# apa102.net
KiCad netlist of a schematic drawn in EAGLE
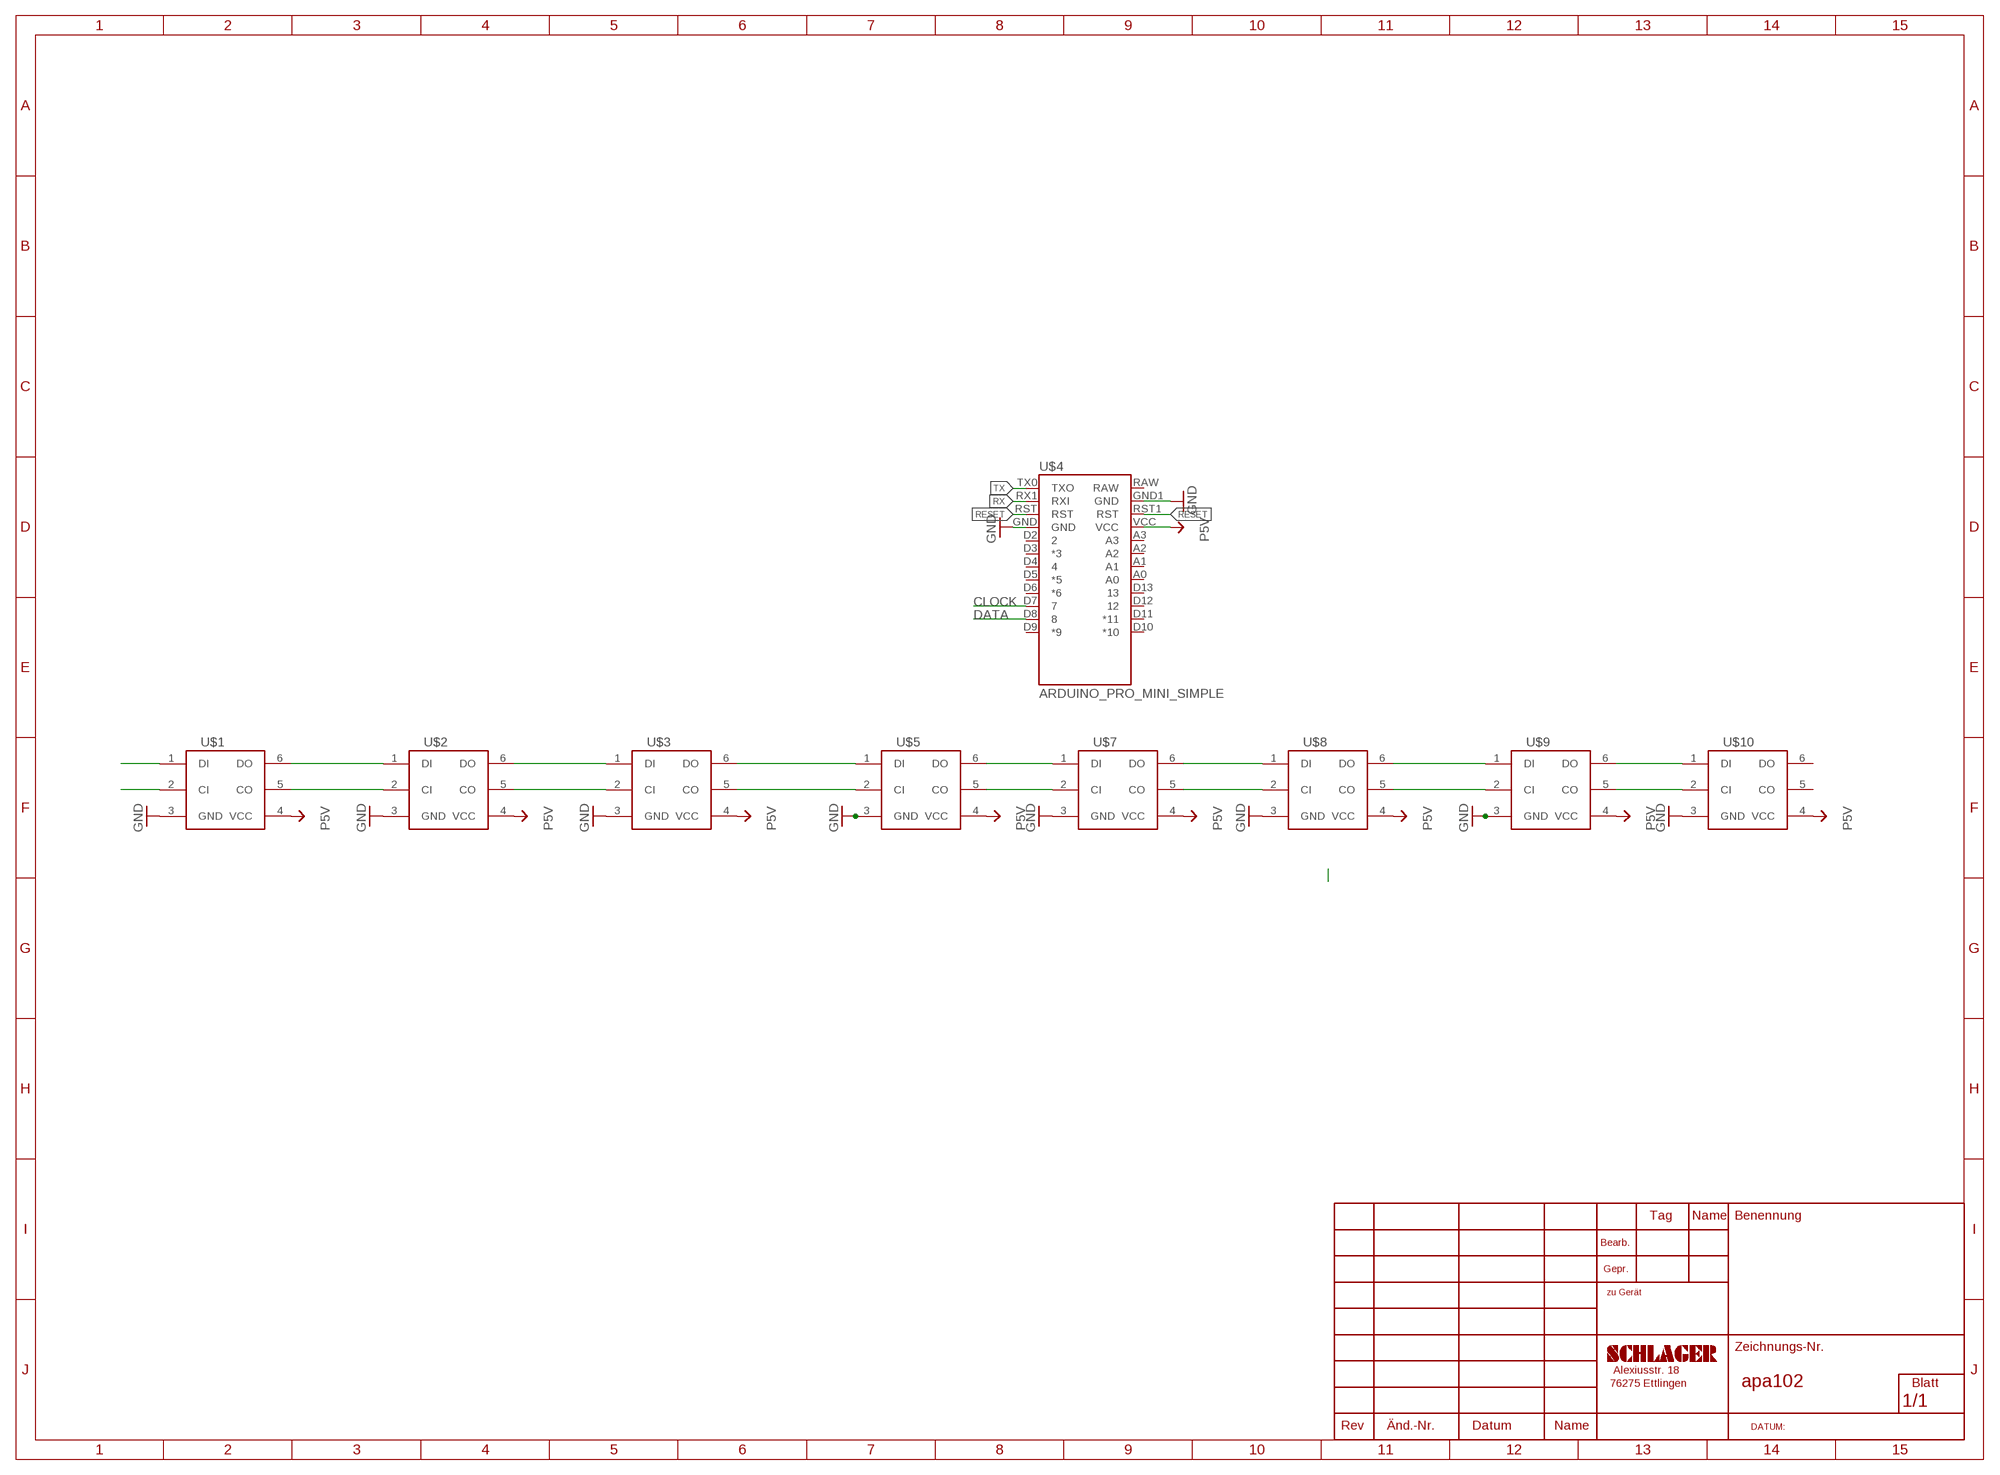
[diagram p0: schematic, sheet 1]

(export (version "E")
  (design (tool "Eeschema 10.0.6"))
  (components
    (comp (ref "U$1")
      (value "APA102")
      (footprint "eagle-import:LED5050")
      (libsource (lib "eagle-import") (part "APA102"))
    )
    (comp (ref "U$2")
      (value "APA102")
      (footprint "eagle-import:LED5050")
      (libsource (lib "eagle-import") (part "APA102"))
    )
    (comp (ref "U$3")
      (value "APA102")
      (footprint "eagle-import:LED5050")
      (libsource (lib "eagle-import") (part "APA102"))
    )
    (comp (ref "U$4")
      (value "ARDUINO_PRO_MINI_SIMPLE")
      (footprint "eagle-import:PRO_MINI_SIMPLE")
      (libsource (lib "eagle-import") (part "ARDUINO_PRO_MINI_SIMPLE"))
    )
    (comp (ref "U$5")
      (value "APA102")
      (footprint "eagle-import:LED5050")
      (libsource (lib "eagle-import") (part "APA102"))
    )
    (comp (ref "U$7")
      (value "APA102")
      (footprint "eagle-import:LED5050")
      (libsource (lib "eagle-import") (part "APA102"))
    )
    (comp (ref "U$8")
      (value "APA102")
      (footprint "eagle-import:LED5050")
      (libsource (lib "eagle-import") (part "APA102"))
    )
    (comp (ref "U$9")
      (value "APA102")
      (footprint "eagle-import:LED5050")
      (libsource (lib "eagle-import") (part "APA102"))
    )
    (comp (ref "U$10")
      (value "APA102")
      (footprint "eagle-import:LED5050")
      (libsource (lib "eagle-import") (part "APA102"))
    )
  )
  (nets
    (net (code "1") (name "/CLOCK") (class "Default")
      (node (ref "U$1") (pin "2") (pinfunction "CI_2") (pintype "bidirectional"))
      (node (ref "U$4") (pin "D7") (pinfunction "7_D7") (pintype "bidirectional"))
    )
    (net (code "2") (name "/DATA") (class "Default")
      (node (ref "U$1") (pin "1") (pinfunction "DI_1") (pintype "bidirectional"))
      (node (ref "U$4") (pin "D8") (pinfunction "8_D8") (pintype "bidirectional"))
    )
    (net (code "3") (name "GND") (class "Default")
      (node (ref "U$1") (pin "3") (pinfunction "GND_3") (pintype "bidirectional"))
      (node (ref "U$10") (pin "3") (pinfunction "GND_3") (pintype "bidirectional"))
      (node (ref "U$2") (pin "3") (pinfunction "GND_3") (pintype "bidirectional"))
      (node (ref "U$3") (pin "3") (pinfunction "GND_3") (pintype "bidirectional"))
      (node (ref "U$4") (pin "GND") (pinfunction "GND_GND") (pintype "bidirectional"))
      (node (ref "U$4") (pin "GND1") (pinfunction "GND_GND1") (pintype "bidirectional"))
      (node (ref "U$5") (pin "3") (pinfunction "GND_3") (pintype "bidirectional"))
      (node (ref "U$7") (pin "3") (pinfunction "GND_3") (pintype "bidirectional"))
      (node (ref "U$8") (pin "3") (pinfunction "GND_3") (pintype "bidirectional"))
      (node (ref "U$9") (pin "3") (pinfunction "GND_3") (pintype "bidirectional"))
    )
    (net (code "4") (name "Net-(U$1-CO)") (class "Default")
      (node (ref "U$1") (pin "5") (pinfunction "CO_5") (pintype "bidirectional"))
      (node (ref "U$2") (pin "2") (pinfunction "CI_2") (pintype "bidirectional"))
    )
    (net (code "5") (name "Net-(U$1-DO)") (class "Default")
      (node (ref "U$1") (pin "6") (pinfunction "DO_6") (pintype "bidirectional"))
      (node (ref "U$2") (pin "1") (pinfunction "DI_1") (pintype "bidirectional"))
    )
    (net (code "6") (name "Net-(U$2-CO)") (class "Default")
      (node (ref "U$2") (pin "5") (pinfunction "CO_5") (pintype "bidirectional"))
      (node (ref "U$3") (pin "2") (pinfunction "CI_2") (pintype "bidirectional"))
    )
    (net (code "7") (name "Net-(U$2-DO)") (class "Default")
      (node (ref "U$2") (pin "6") (pinfunction "DO_6") (pintype "bidirectional"))
      (node (ref "U$3") (pin "1") (pinfunction "DI_1") (pintype "bidirectional"))
    )
    (net (code "8") (name "Net-(U$3-CO)") (class "Default")
      (node (ref "U$3") (pin "5") (pinfunction "CO_5") (pintype "bidirectional"))
      (node (ref "U$5") (pin "2") (pinfunction "CI_2") (pintype "bidirectional"))
    )
    (net (code "9") (name "Net-(U$3-DO)") (class "Default")
      (node (ref "U$3") (pin "6") (pinfunction "DO_6") (pintype "bidirectional"))
      (node (ref "U$5") (pin "1") (pinfunction "DI_1") (pintype "bidirectional"))
    )
    (net (code "10") (name "Net-(U$5-CO)") (class "Default")
      (node (ref "U$5") (pin "5") (pinfunction "CO_5") (pintype "bidirectional"))
      (node (ref "U$7") (pin "2") (pinfunction "CI_2") (pintype "bidirectional"))
    )
    (net (code "11") (name "Net-(U$5-DO)") (class "Default")
      (node (ref "U$5") (pin "6") (pinfunction "DO_6") (pintype "bidirectional"))
      (node (ref "U$7") (pin "1") (pinfunction "DI_1") (pintype "bidirectional"))
    )
    (net (code "12") (name "Net-(U$7-CO)") (class "Default")
      (node (ref "U$7") (pin "5") (pinfunction "CO_5") (pintype "bidirectional"))
      (node (ref "U$8") (pin "2") (pinfunction "CI_2") (pintype "bidirectional"))
    )
    (net (code "13") (name "Net-(U$7-DO)") (class "Default")
      (node (ref "U$7") (pin "6") (pinfunction "DO_6") (pintype "bidirectional"))
      (node (ref "U$8") (pin "1") (pinfunction "DI_1") (pintype "bidirectional"))
    )
    (net (code "14") (name "Net-(U$8-CO)") (class "Default")
      (node (ref "U$8") (pin "5") (pinfunction "CO_5") (pintype "bidirectional"))
      (node (ref "U$9") (pin "2") (pinfunction "CI_2") (pintype "bidirectional"))
    )
    (net (code "15") (name "Net-(U$8-DO)") (class "Default")
      (node (ref "U$8") (pin "6") (pinfunction "DO_6") (pintype "bidirectional"))
      (node (ref "U$9") (pin "1") (pinfunction "DI_1") (pintype "bidirectional"))
    )
    (net (code "16") (name "Net-(U$10-CI)") (class "Default")
      (node (ref "U$10") (pin "2") (pinfunction "CI_2") (pintype "bidirectional"))
      (node (ref "U$9") (pin "5") (pinfunction "CO_5") (pintype "bidirectional"))
    )
    (net (code "17") (name "Net-(U$10-DI)") (class "Default")
      (node (ref "U$10") (pin "1") (pinfunction "DI_1") (pintype "bidirectional"))
      (node (ref "U$9") (pin "6") (pinfunction "DO_6") (pintype "bidirectional"))
    )
    (net (code "18") (name "P5V") (class "Default")
      (node (ref "U$1") (pin "4") (pinfunction "VCC_4") (pintype "bidirectional"))
      (node (ref "U$10") (pin "4") (pinfunction "VCC_4") (pintype "bidirectional"))
      (node (ref "U$2") (pin "4") (pinfunction "VCC_4") (pintype "bidirectional"))
      (node (ref "U$3") (pin "4") (pinfunction "VCC_4") (pintype "bidirectional"))
      (node (ref "U$4") (pin "VCC") (pinfunction "VCC_VCC") (pintype "bidirectional"))
      (node (ref "U$5") (pin "4") (pinfunction "VCC_4") (pintype "bidirectional"))
      (node (ref "U$7") (pin "4") (pinfunction "VCC_4") (pintype "bidirectional"))
      (node (ref "U$8") (pin "4") (pinfunction "VCC_4") (pintype "bidirectional"))
      (node (ref "U$9") (pin "4") (pinfunction "VCC_4") (pintype "bidirectional"))
    )
    (net (code "19") (name "RESET") (class "Default")
      (node (ref "U$4") (pin "RST") (pinfunction "RST_RST") (pintype "bidirectional"))
      (node (ref "U$4") (pin "RST1") (pinfunction "RST_RST1") (pintype "bidirectional"))
    )
    (net (code "20") (name "RX") (class "Default")
      (node (ref "U$4") (pin "RX1") (pinfunction "RXI_RX1") (pintype "bidirectional"))
    )
    (net (code "21") (name "TX") (class "Default")
      (node (ref "U$4") (pin "TX0") (pinfunction "TXO_TX0") (pintype "bidirectional"))
    )
    (net (code "22") (name "unconnected-(U$4-*3-PadD3)") (class "Default")
      (node (ref "U$4") (pin "D3") (pinfunction "*3_D3") (pintype "bidirectional"))
    )
    (net (code "23") (name "unconnected-(U$4-*5-PadD5)") (class "Default")
      (node (ref "U$4") (pin "D5") (pinfunction "*5_D5") (pintype "bidirectional"))
    )
    (net (code "24") (name "unconnected-(U$4-*6-PadD6)") (class "Default")
      (node (ref "U$4") (pin "D6") (pinfunction "*6_D6") (pintype "bidirectional"))
    )
    (net (code "25") (name "unconnected-(U$4-*9-PadD9)") (class "Default")
      (node (ref "U$4") (pin "D9") (pinfunction "*9_D9") (pintype "bidirectional"))
    )
    (net (code "26") (name "unconnected-(U$4-*10-PadD10)") (class "Default")
      (node (ref "U$4") (pin "D10") (pinfunction "*10_D10") (pintype "bidirectional"))
    )
    (net (code "27") (name "unconnected-(U$4-*11-PadD11)") (class "Default")
      (node (ref "U$4") (pin "D11") (pinfunction "*11_D11") (pintype "bidirectional"))
    )
    (net (code "28") (name "unconnected-(U$4-2-PadD2)") (class "Default")
      (node (ref "U$4") (pin "D2") (pinfunction "2_D2") (pintype "bidirectional"))
    )
    (net (code "29") (name "unconnected-(U$4-4-PadD4)") (class "Default")
      (node (ref "U$4") (pin "D4") (pinfunction "4_D4") (pintype "bidirectional"))
    )
    (net (code "30") (name "unconnected-(U$4-12-PadD12)") (class "Default")
      (node (ref "U$4") (pin "D12") (pinfunction "12_D12") (pintype "bidirectional"))
    )
    (net (code "31") (name "unconnected-(U$4-13-PadD13)") (class "Default")
      (node (ref "U$4") (pin "D13") (pinfunction "13_D13") (pintype "bidirectional"))
    )
    (net (code "32") (name "unconnected-(U$4-PadA0)") (class "Default")
      (node (ref "U$4") (pin "A0") (pinfunction "A0_A0") (pintype "bidirectional"))
    )
    (net (code "33") (name "unconnected-(U$4-PadA1)") (class "Default")
      (node (ref "U$4") (pin "A1") (pinfunction "A1_A1") (pintype "bidirectional"))
    )
    (net (code "34") (name "unconnected-(U$4-PadA2)") (class "Default")
      (node (ref "U$4") (pin "A2") (pinfunction "A2_A2") (pintype "bidirectional"))
    )
    (net (code "35") (name "unconnected-(U$4-PadA3)") (class "Default")
      (node (ref "U$4") (pin "A3") (pinfunction "A3_A3") (pintype "bidirectional"))
    )
    (net (code "36") (name "unconnected-(U$4-PadRAW)") (class "Default")
      (node (ref "U$4") (pin "RAW") (pinfunction "RAW_RAW") (pintype "bidirectional"))
    )
    (net (code "37") (name "unconnected-(U$10-CO-Pad5)") (class "Default")
      (node (ref "U$10") (pin "5") (pinfunction "CO_5") (pintype "bidirectional"))
    )
    (net (code "38") (name "unconnected-(U$10-DO-Pad6)") (class "Default")
      (node (ref "U$10") (pin "6") (pinfunction "DO_6") (pintype "bidirectional"))
    )
  )
)
